# DAC.net
KiCad netlist of a schematic drawn in Altium Designer
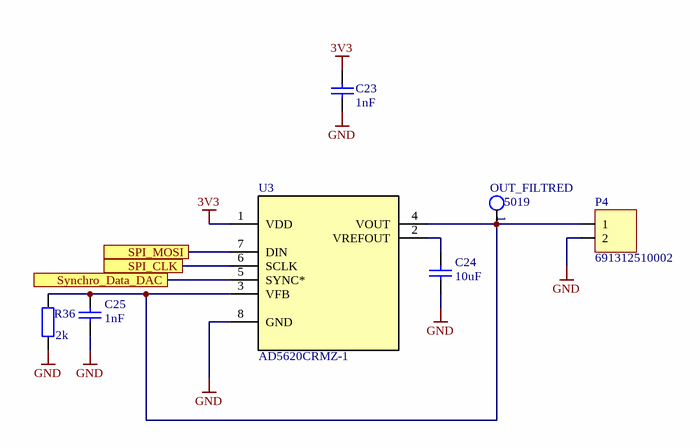
[diagram p0: DAC.SchDoc]

(export (version "E")
  (design (tool "Eeschema 10.0.6"))
  (components
    (comp (ref "C23")
      (value "1nF")
      (footprint "C0805")
      (description "Capacitor")
      (fields (field (name "PUBLISHER") "Altium Limited"))
      (libsource (lib "Miscellaneous Devices") (part "Cap"))
    )
    (comp (ref "C24")
      (value "10uF")
      (footprint "C0805")
      (description "Capacitor")
      (fields (field (name "PUBLISHER") "Altium Limited"))
      (libsource (lib "Miscellaneous Devices") (part "Cap"))
    )
    (comp (ref "C25")
      (value "1nF")
      (footprint "C0805")
      (description "Capacitor")
      (fields (field (name "PUBLISHER") "Altium Limited"))
      (libsource (lib "Miscellaneous Devices") (part "Cap"))
    )
    (comp (ref "OUT_FILTRED")
      (value "5019")
      (footprint "KEYSTONE_5019")
      (fields (field (name "MANUFACTURER") "Keystone Electronics"))
      (libsource (lib "2225B_VumetreFrequenciel") (part "CMP-1672-00008-2"))
    )
    (comp (ref "P4")
      (value "691312510002")
      (footprint "LINX_CONBNC002")
      (description "Header, 2-Pin")
      (fields (field (name "PUBLISHER") "Altium Limited"))
      (libsource (lib "2225B_VumetreFrequenciel") (part "MHDR1X2"))
    )
    (comp (ref "R36")
      (value "2k")
      (footprint "RESC2012X06M")
      (description "Resistor")
      (fields (field (name "PUBLISHER") "Altium Limited"))
      (libsource (lib "Miscellaneous Devices") (part "Res2"))
    )
    (comp (ref "U3")
      (value "AD5620CRMZ-1")
      (footprint "SOP65P490X110-8N")
      (description "Single, 12-Bit nanoDACÂ® with 5 ppm/Â°C On-Chip Reference in SOT-23")
      (fields (field (name "MF") "Analog Devices"))
      (libsource (lib "2227_BoiteBruitage") (part "AD5620CRMZ-1"))
    )
  )
  (nets
    (net (code "1") (name "/SPI_CLK") (class "Default")
      (node (ref "U3") (pin "6") (pinfunction "SCLK_6") (pintype "passive"))
    )
    (net (code "2") (name "/SPI_MOSI") (class "Default")
      (node (ref "U3") (pin "7") (pinfunction "DIN_7") (pintype "passive"))
    )
    (net (code "3") (name "/Synchro_Data_DAC") (class "Default")
      (node (ref "U3") (pin "5") (pinfunction "SYNC*_5") (pintype "passive"))
    )
    (net (code "4") (name "3V3") (class "Default")
      (node (ref "C23") (pin "2") (pinfunction "2_2") (pintype "passive"))
      (node (ref "U3") (pin "1") (pinfunction "VDD_1") (pintype "power_in"))
    )
    (net (code "5") (name "GND") (class "Default")
      (node (ref "C23") (pin "1") (pinfunction "1_1") (pintype "passive"))
      (node (ref "C24") (pin "1") (pinfunction "1_1") (pintype "passive"))
      (node (ref "C25") (pin "1") (pinfunction "1_1") (pintype "passive"))
      (node (ref "P4") (pin "2") (pinfunction "2_2") (pintype "passive"))
      (node (ref "R36") (pin "1") (pinfunction "1_1") (pintype "passive"))
      (node (ref "U3") (pin "8") (pinfunction "GND_8") (pintype "passive"))
    )
    (net (code "6") (name "Net-(U3-VFB)") (class "Default")
      (node (ref "C25") (pin "2") (pinfunction "2_2") (pintype "passive"))
      (node (ref "OUT_FILTRED") (pin "1") (pinfunction "1_1") (pintype "passive"))
      (node (ref "P4") (pin "1") (pinfunction "1_1") (pintype "passive"))
      (node (ref "R36") (pin "2") (pinfunction "2_2") (pintype "passive"))
      (node (ref "U3") (pin "3") (pinfunction "VFB_3") (pintype "passive"))
      (node (ref "U3") (pin "4") (pinfunction "VOUT_4") (pintype "passive"))
    )
    (net (code "7") (name "Net-(U3-VREFOUT)") (class "Default")
      (node (ref "C24") (pin "2") (pinfunction "2_2") (pintype "passive"))
      (node (ref "U3") (pin "2") (pinfunction "VREFOUT_2") (pintype "passive"))
    )
  )
)
